# lv.net
KiCad netlist of a schematic drawn in Altium Designer
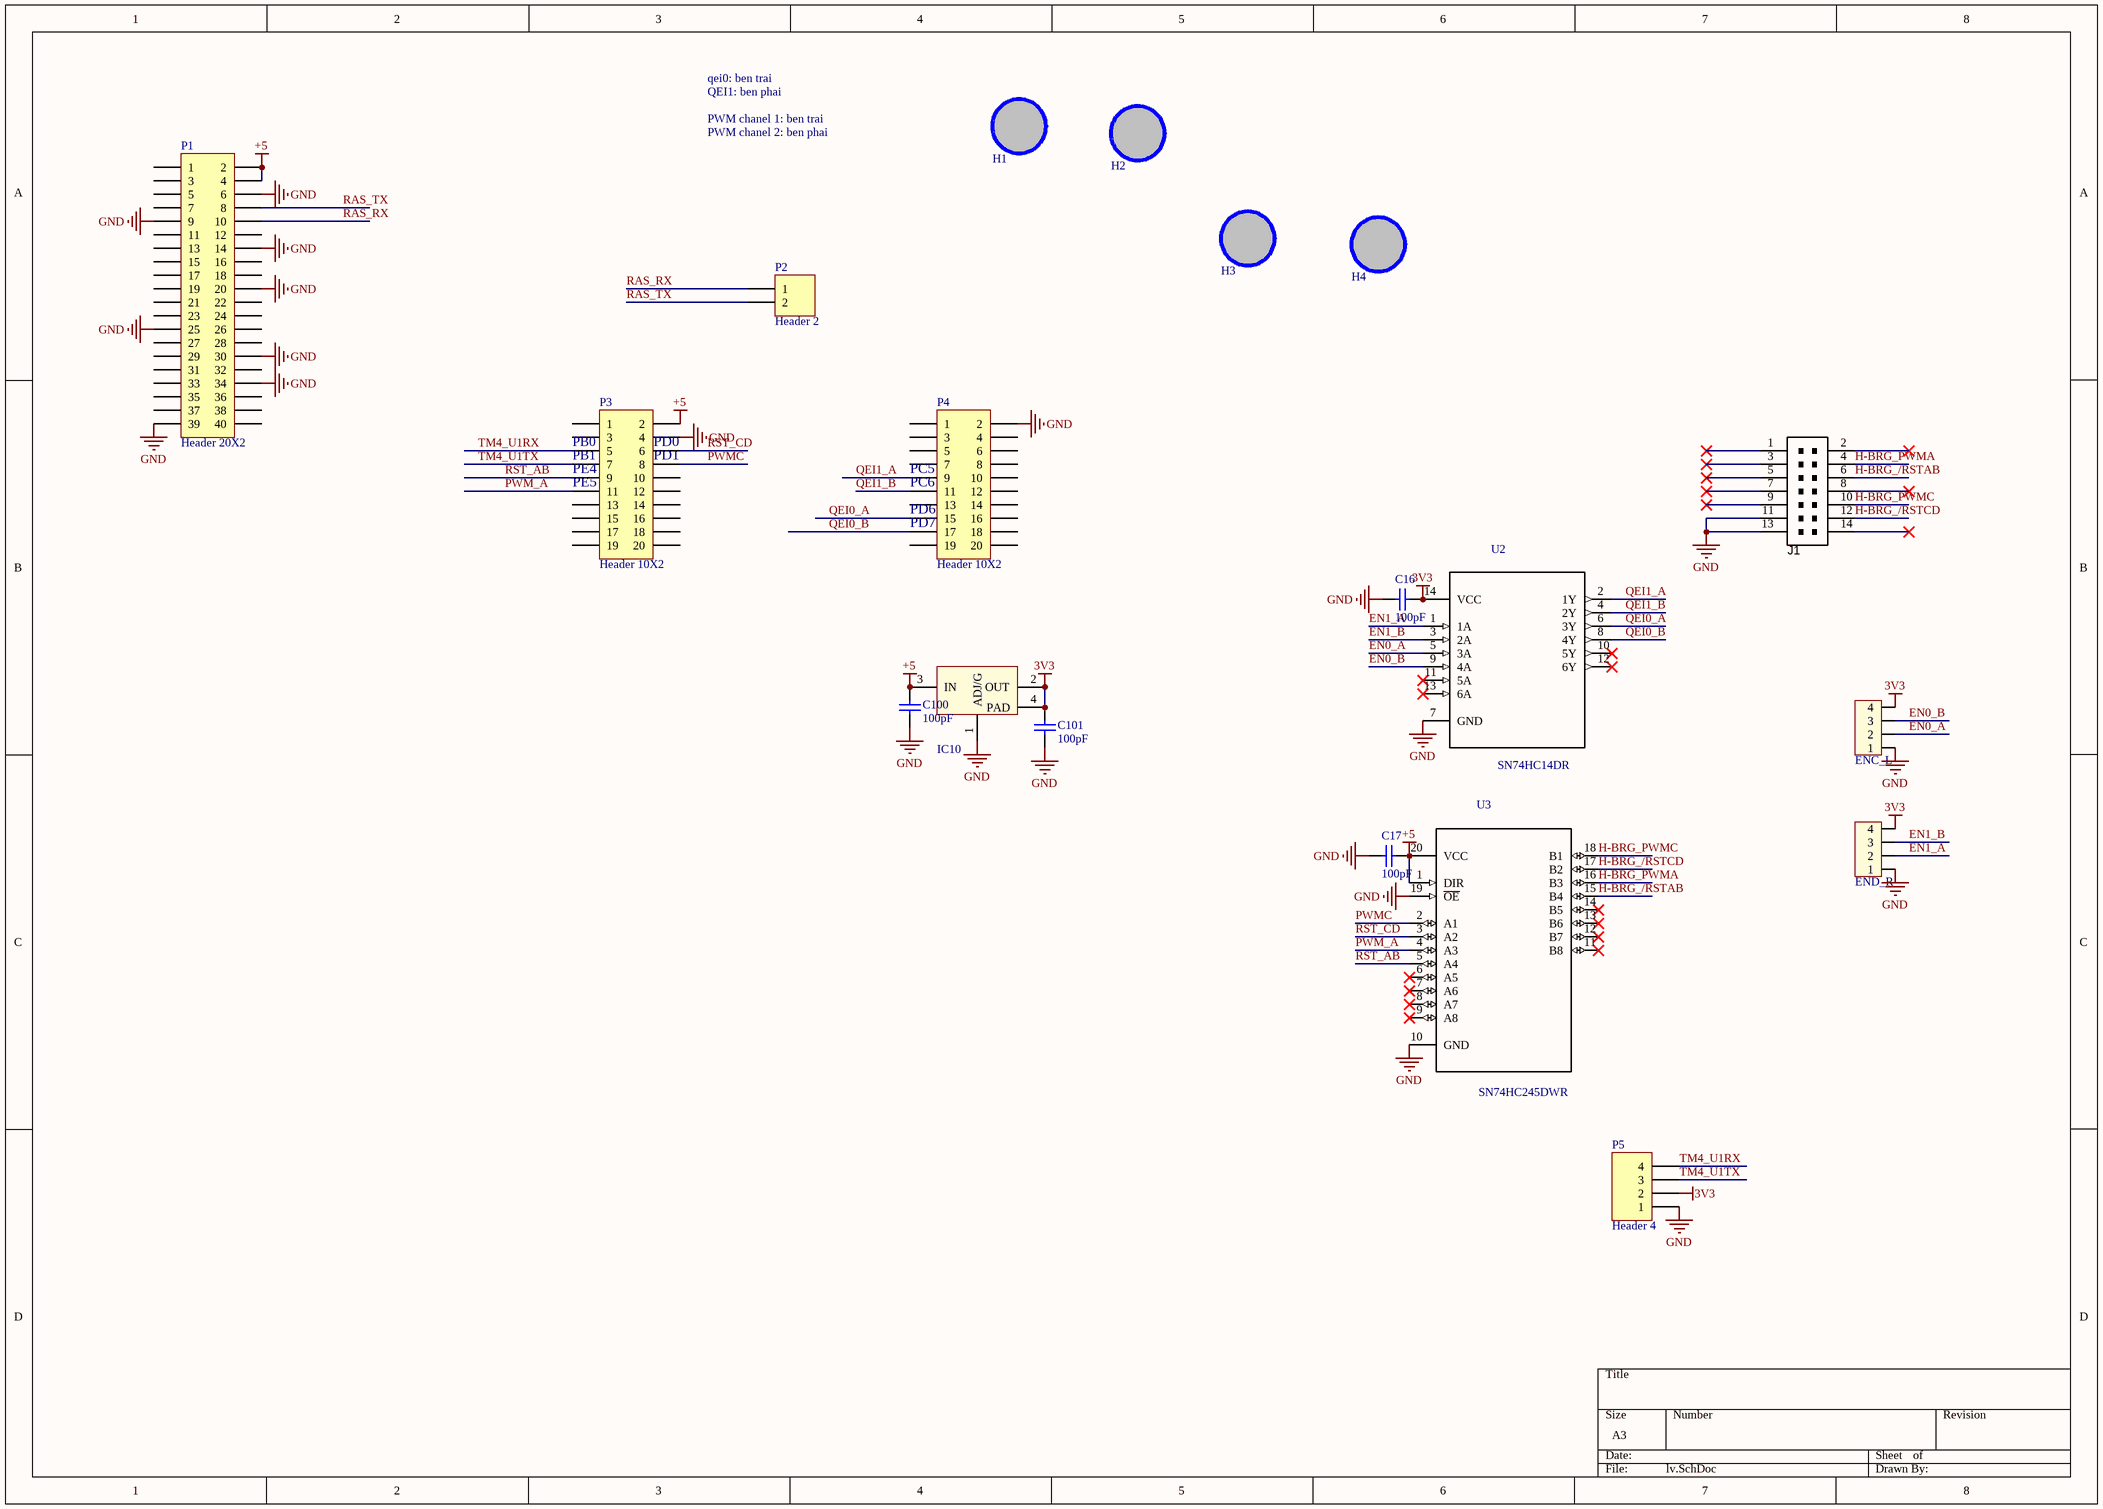
[diagram p0: lv.SchDoc]

(export (version "E")
  (design (tool "Eeschema 10.0.6"))
  (components
    (comp (ref "C16")
      (value "100pF")
      (footprint "CAP-SM-0805")
      (description "Capacitor")
      (fields (field (name "Comment") "Cap Non-Pol SMD"))
      (libsource (lib "PIF_Library") (part "Cap Non-Pol SMD"))
    )
    (comp (ref "C17")
      (value "100pF")
      (footprint "CAP-SM-0805")
      (description "Capacitor")
      (fields (field (name "Comment") "Cap Non-Pol SMD"))
      (libsource (lib "PIF_Library") (part "Cap Non-Pol SMD"))
    )
    (comp (ref "C100")
      (value "100pF")
      (footprint "CAP-SM-0805")
      (description "Capacitor")
      (fields (field (name "Comment") "Cap Non-Pol SMD"))
      (libsource (lib "PIF_Library") (part "Cap Non-Pol SMD"))
    )
    (comp (ref "C101")
      (value "100pF")
      (footprint "CAP-SM-0805")
      (description "Capacitor")
      (fields (field (name "Comment") "Cap Non-Pol SMD"))
      (libsource (lib "PIF_Library") (part "Cap Non-Pol SMD"))
    )
    (comp (ref "ENC_L1")
      (value "ENC_L")
      (footprint "CON4")
      (description "Connector 4")
      (libsource (lib "tuanti1997qn") (part "Con4"))
    )
    (comp (ref "END_R1")
      (value "END_R")
      (footprint "CON4")
      (description "Connector 4")
      (libsource (lib "tuanti1997qn") (part "Con4"))
    )
    (comp (ref "H1")
      (value "Hole")
      (footprint "LO KHOAN 3MM")
      (description "Hole 3mm")
      (libsource (lib "PIF_Library") (part "Hole"))
    )
    (comp (ref "H2")
      (value "Hole")
      (footprint "LO KHOAN 3MM")
      (description "Hole 3mm")
      (libsource (lib "PIF_Library") (part "Hole"))
    )
    (comp (ref "H3")
      (value "Hole")
      (footprint "LO KHOAN 3MM")
      (description "Hole 3mm")
      (libsource (lib "PIF_Library") (part "Hole"))
    )
    (comp (ref "H4")
      (value "Hole")
      (footprint "LO KHOAN 3MM")
      (description "Hole 3mm")
      (libsource (lib "PIF_Library") (part "Hole"))
    )
    (comp (ref "IC10")
      (value "LM1117")
      (footprint "SOT223-4N")
      (description "Available in 1.8V, 2.5V, 2.85V, 3.3V, 5V, and  Adjustable Versions")
      (libsource (lib "PIF_Library") (part "LM1117"))
    )
    (comp (ref "J1")
      (value "shrouded box header")
      (footprint "14P_PCB_HEADER_BRD_MNT_RA")
      (description "Header THD 14 POS Double-row right-angle 2.54mm pitch")
      (libsource (lib "tuanti1997qn") (part "CONN_HEADER_2x7P_RA_0.100in_Male"))
    )
    (comp (ref "P1")
      (value "Header 20X2")
      (footprint "HDR2X20")
      (description "Header, 20-Pin, Dual row")
      (fields (field (name "PUBLISHER") "Altium Limited"))
      (libsource (lib "Miscellaneous Connectors") (part "Header 20X2"))
    )
    (comp (ref "P2")
      (value "Header 2")
      (footprint "HDR1X2")
      (description "Header, 2-Pin")
      (fields (field (name "PUBLISHER") "Altium Limited"))
      (libsource (lib "Miscellaneous Connectors") (part "Header 2"))
    )
    (comp (ref "P3")
      (value "Header 10X2")
      (footprint "HDR2X10")
      (description "Header, 10-Pin, Dual row")
      (fields (field (name "PUBLISHER") "Altium Limited"))
      (libsource (lib "Miscellaneous Connectors") (part "Header 10X2"))
    )
    (comp (ref "P4")
      (value "Header 10X2")
      (footprint "HDR2X10")
      (description "Header, 10-Pin, Dual row")
      (fields (field (name "PUBLISHER") "Altium Limited"))
      (libsource (lib "Miscellaneous Connectors") (part "Header 10X2"))
    )
    (comp (ref "P5")
      (value "Header 4")
      (footprint "HDR1X4")
      (description "Header, 4-Pin")
      (fields (field (name "PUBLISHER") "Altium Limited"))
      (libsource (lib "Miscellaneous Connectors") (part "Header 4"))
    )
    (comp (ref "U2")
      (value "SN74HC14DR")
      (footprint "*SOIC127P600X175-14N")
      (description "Inverter Schmitt Trigger 6-Element CMOS 14-Pin SOIC T/R")
      (fields (field (name "MF") "Texas Instruments"))
      (libsource (lib "SN74HC14DR") (part "SN74HC14DR"))
    )
    (comp (ref "U3")
      (value "SN74HC245DWR")
      (footprint "*SOIC127P1030X265-20N")
      (description "Logic IC - Receiver, transceiver Texas Instruments SN74HC245DWR SOIC 20")
      (fields (field (name "MF") "Texas Instruments"))
      (libsource (lib "SN74HC245DWR") (part "SN74HC245DWR"))
    )
  )
  (nets
    (net (code "1") (name "+5") (class "Default")
      (node (ref "C100") (pin "2") (pinfunction "2_2") (pintype "passive"))
      (node (ref "C17") (pin "1") (pinfunction "1_1") (pintype "passive"))
      (node (ref "IC10") (pin "3") (pinfunction "IN_3") (pintype "passive"))
      (node (ref "P1") (pin "2") (pinfunction "2_2") (pintype "passive"))
      (node (ref "P1") (pin "4") (pinfunction "4_4") (pintype "passive"))
      (node (ref "P3") (pin "2") (pinfunction "2_2") (pintype "passive"))
      (node (ref "U3") (pin "1") (pinfunction "DIR_1") (pintype "input"))
      (node (ref "U3") (pin "20") (pinfunction "VCC_20") (pintype "power_in"))
    )
    (net (code "2") (name "/EN0_A") (class "Default")
      (node (ref "ENC_L1") (pin "2") (pinfunction "2_2") (pintype "passive"))
      (node (ref "U2") (pin "5") (pinfunction "3A_5") (pintype "input"))
    )
    (net (code "3") (name "/EN0_B") (class "Default")
      (node (ref "ENC_L1") (pin "3") (pinfunction "3_3") (pintype "passive"))
      (node (ref "U2") (pin "9") (pinfunction "4A_9") (pintype "input"))
    )
    (net (code "4") (name "/EN1_A") (class "Default")
      (node (ref "END_R1") (pin "2") (pinfunction "2_2") (pintype "passive"))
      (node (ref "U2") (pin "1") (pinfunction "1A_1") (pintype "input"))
    )
    (net (code "5") (name "/EN1_B") (class "Default")
      (node (ref "END_R1") (pin "3") (pinfunction "3_3") (pintype "passive"))
      (node (ref "U2") (pin "3") (pinfunction "2A_3") (pintype "input"))
    )
    (net (code "6") (name "/H-BRG_PWMA") (class "Default")
      (node (ref "J1") (pin "4") (pinfunction "4_4") (pintype "passive"))
      (node (ref "U3") (pin "16") (pinfunction "B3_16") (pintype "bidirectional"))
    )
    (net (code "7") (name "/H-BRG_PWMC") (class "Default")
      (node (ref "J1") (pin "10") (pinfunction "10_10") (pintype "passive"))
      (node (ref "U3") (pin "18") (pinfunction "B1_18") (pintype "bidirectional"))
    )
    (net (code "8") (name "/H-BRG_{slash}RSTAB") (class "Default")
      (node (ref "J1") (pin "6") (pinfunction "6_6") (pintype "passive"))
      (node (ref "U3") (pin "15") (pinfunction "B4_15") (pintype "bidirectional"))
    )
    (net (code "9") (name "/H-BRG_{slash}RSTCD") (class "Default")
      (node (ref "J1") (pin "12") (pinfunction "12_12") (pintype "passive"))
      (node (ref "U3") (pin "17") (pinfunction "B2_17") (pintype "bidirectional"))
    )
    (net (code "10") (name "/PWMC") (class "Default")
      (node (ref "P3") (pin "8") (pinfunction "8_8") (pintype "passive"))
      (node (ref "U3") (pin "2") (pinfunction "A1_2") (pintype "bidirectional"))
    )
    (net (code "11") (name "/PWM_A") (class "Default")
      (node (ref "P3") (pin "11") (pinfunction "11_11") (pintype "passive"))
      (node (ref "U3") (pin "4") (pinfunction "A3_4") (pintype "bidirectional"))
    )
    (net (code "12") (name "/QEI0_A") (class "Default")
      (node (ref "P4") (pin "15") (pinfunction "15_15") (pintype "passive"))
      (node (ref "U2") (pin "6") (pinfunction "3Y_6") (pintype "output"))
    )
    (net (code "13") (name "/QEI0_B") (class "Default")
      (node (ref "P4") (pin "17") (pinfunction "17_17") (pintype "passive"))
      (node (ref "U2") (pin "8") (pinfunction "4Y_8") (pintype "output"))
    )
    (net (code "14") (name "/QEI1_A") (class "Default")
      (node (ref "P4") (pin "9") (pinfunction "9_9") (pintype "passive"))
      (node (ref "U2") (pin "2") (pinfunction "1Y_2") (pintype "output"))
    )
    (net (code "15") (name "/QEI1_B") (class "Default")
      (node (ref "P4") (pin "11") (pinfunction "11_11") (pintype "passive"))
      (node (ref "U2") (pin "4") (pinfunction "2Y_4") (pintype "output"))
    )
    (net (code "16") (name "/RAS_RX") (class "Default")
      (node (ref "P1") (pin "10") (pinfunction "10_10") (pintype "passive"))
      (node (ref "P2") (pin "1") (pinfunction "1_1") (pintype "passive"))
    )
    (net (code "17") (name "/RAS_TX") (class "Default")
      (node (ref "P1") (pin "8") (pinfunction "8_8") (pintype "passive"))
      (node (ref "P2") (pin "2") (pinfunction "2_2") (pintype "passive"))
    )
    (net (code "18") (name "/RST_AB") (class "Default")
      (node (ref "P3") (pin "9") (pinfunction "9_9") (pintype "passive"))
      (node (ref "U3") (pin "5") (pinfunction "A4_5") (pintype "bidirectional"))
    )
    (net (code "19") (name "/RST_CD") (class "Default")
      (node (ref "P3") (pin "6") (pinfunction "6_6") (pintype "passive"))
      (node (ref "U3") (pin "3") (pinfunction "A2_3") (pintype "bidirectional"))
    )
    (net (code "20") (name "/TM4_U1RX") (class "Default")
      (node (ref "P3") (pin "5") (pinfunction "5_5") (pintype "passive"))
      (node (ref "P5") (pin "4") (pinfunction "4_4") (pintype "passive"))
    )
    (net (code "21") (name "/TM4_U1TX") (class "Default")
      (node (ref "P3") (pin "7") (pinfunction "7_7") (pintype "passive"))
      (node (ref "P5") (pin "3") (pinfunction "3_3") (pintype "passive"))
    )
    (net (code "22") (name "3V3") (class "Default")
      (node (ref "C101") (pin "2") (pinfunction "2_2") (pintype "passive"))
      (node (ref "C16") (pin "1") (pinfunction "1_1") (pintype "passive"))
      (node (ref "ENC_L1") (pin "4") (pinfunction "4_4") (pintype "passive"))
      (node (ref "END_R1") (pin "4") (pinfunction "4_4") (pintype "passive"))
      (node (ref "IC10") (pin "2") (pinfunction "OUT_2") (pintype "passive"))
      (node (ref "IC10") (pin "4") (pinfunction "PAD_4") (pintype "passive"))
      (node (ref "P5") (pin "2") (pinfunction "2_2") (pintype "passive"))
      (node (ref "U2") (pin "14") (pinfunction "VCC_14") (pintype "power_in"))
    )
    (net (code "23") (name "GND") (class "Default")
      (node (ref "C100") (pin "1") (pinfunction "1_1") (pintype "passive"))
      (node (ref "C101") (pin "1") (pinfunction "1_1") (pintype "passive"))
      (node (ref "C16") (pin "2") (pinfunction "2_2") (pintype "passive"))
      (node (ref "C17") (pin "2") (pinfunction "2_2") (pintype "passive"))
      (node (ref "ENC_L1") (pin "1") (pinfunction "1_1") (pintype "passive"))
      (node (ref "END_R1") (pin "1") (pinfunction "1_1") (pintype "passive"))
      (node (ref "IC10") (pin "1") (pinfunction "ADJ/G_1") (pintype "passive"))
      (node (ref "J1") (pin "11") (pinfunction "11_11") (pintype "passive"))
      (node (ref "J1") (pin "13") (pinfunction "13_13") (pintype "passive"))
      (node (ref "P1") (pin "14") (pinfunction "14_14") (pintype "passive"))
      (node (ref "P1") (pin "20") (pinfunction "20_20") (pintype "passive"))
      (node (ref "P1") (pin "25") (pinfunction "25_25") (pintype "passive"))
      (node (ref "P1") (pin "30") (pinfunction "30_30") (pintype "passive"))
      (node (ref "P1") (pin "34") (pinfunction "34_34") (pintype "passive"))
      (node (ref "P1") (pin "39") (pinfunction "39_39") (pintype "passive"))
      (node (ref "P1") (pin "6") (pinfunction "6_6") (pintype "passive"))
      (node (ref "P1") (pin "9") (pinfunction "9_9") (pintype "passive"))
      (node (ref "P3") (pin "4") (pinfunction "4_4") (pintype "passive"))
      (node (ref "P4") (pin "2") (pinfunction "2_2") (pintype "passive"))
      (node (ref "P5") (pin "1") (pinfunction "1_1") (pintype "passive"))
      (node (ref "U2") (pin "7") (pinfunction "GND_7") (pintype "passive"))
      (node (ref "U3") (pin "10") (pinfunction "GND_10") (pintype "passive"))
      (node (ref "U3") (pin "19") (pinfunction "~{OE}_19") (pintype "input"))
    )
    (net (code "24") (name "unconnected-(H1-Pad1)") (class "Default")
      (node (ref "H1") (pin "1") (pinfunction "1_1") (pintype "passive"))
    )
    (net (code "25") (name "unconnected-(H2-Pad1)") (class "Default")
      (node (ref "H2") (pin "1") (pinfunction "1_1") (pintype "passive"))
    )
    (net (code "26") (name "unconnected-(H3-Pad1)") (class "Default")
      (node (ref "H3") (pin "1") (pinfunction "1_1") (pintype "passive"))
    )
    (net (code "27") (name "unconnected-(H4-Pad1)") (class "Default")
      (node (ref "H4") (pin "1") (pinfunction "1_1") (pintype "passive"))
    )
    (net (code "28") (name "unconnected-(J1-Pad1)") (class "Default")
      (node (ref "J1") (pin "1") (pinfunction "1_1") (pintype "passive+no_connect"))
    )
    (net (code "29") (name "unconnected-(J1-Pad2)") (class "Default")
      (node (ref "J1") (pin "2") (pinfunction "2_2") (pintype "passive+no_connect"))
    )
    (net (code "30") (name "unconnected-(J1-Pad3)") (class "Default")
      (node (ref "J1") (pin "3") (pinfunction "3_3") (pintype "passive+no_connect"))
    )
    (net (code "31") (name "unconnected-(J1-Pad5)") (class "Default")
      (node (ref "J1") (pin "5") (pinfunction "5_5") (pintype "passive+no_connect"))
    )
    (net (code "32") (name "unconnected-(J1-Pad7)") (class "Default")
      (node (ref "J1") (pin "7") (pinfunction "7_7") (pintype "passive+no_connect"))
    )
    (net (code "33") (name "unconnected-(J1-Pad8)") (class "Default")
      (node (ref "J1") (pin "8") (pinfunction "8_8") (pintype "passive+no_connect"))
    )
    (net (code "34") (name "unconnected-(J1-Pad9)") (class "Default")
      (node (ref "J1") (pin "9") (pinfunction "9_9") (pintype "passive+no_connect"))
    )
    (net (code "35") (name "unconnected-(J1-Pad14)") (class "Default")
      (node (ref "J1") (pin "14") (pinfunction "14_14") (pintype "passive+no_connect"))
    )
    (net (code "36") (name "unconnected-(P1-Pad1)") (class "Default")
      (node (ref "P1") (pin "1") (pinfunction "1_1") (pintype "passive"))
    )
    (net (code "37") (name "unconnected-(P1-Pad3)") (class "Default")
      (node (ref "P1") (pin "3") (pinfunction "3_3") (pintype "passive"))
    )
    (net (code "38") (name "unconnected-(P1-Pad5)") (class "Default")
      (node (ref "P1") (pin "5") (pinfunction "5_5") (pintype "passive"))
    )
    (net (code "39") (name "unconnected-(P1-Pad7)") (class "Default")
      (node (ref "P1") (pin "7") (pinfunction "7_7") (pintype "passive"))
    )
    (net (code "40") (name "unconnected-(P1-Pad11)") (class "Default")
      (node (ref "P1") (pin "11") (pinfunction "11_11") (pintype "passive"))
    )
    (net (code "41") (name "unconnected-(P1-Pad12)") (class "Default")
      (node (ref "P1") (pin "12") (pinfunction "12_12") (pintype "passive"))
    )
    (net (code "42") (name "unconnected-(P1-Pad13)") (class "Default")
      (node (ref "P1") (pin "13") (pinfunction "13_13") (pintype "passive"))
    )
    (net (code "43") (name "unconnected-(P1-Pad15)") (class "Default")
      (node (ref "P1") (pin "15") (pinfunction "15_15") (pintype "passive"))
    )
    (net (code "44") (name "unconnected-(P1-Pad16)") (class "Default")
      (node (ref "P1") (pin "16") (pinfunction "16_16") (pintype "passive"))
    )
    (net (code "45") (name "unconnected-(P1-Pad17)") (class "Default")
      (node (ref "P1") (pin "17") (pinfunction "17_17") (pintype "passive"))
    )
    (net (code "46") (name "unconnected-(P1-Pad18)") (class "Default")
      (node (ref "P1") (pin "18") (pinfunction "18_18") (pintype "passive"))
    )
    (net (code "47") (name "unconnected-(P1-Pad19)") (class "Default")
      (node (ref "P1") (pin "19") (pinfunction "19_19") (pintype "passive"))
    )
    (net (code "48") (name "unconnected-(P1-Pad21)") (class "Default")
      (node (ref "P1") (pin "21") (pinfunction "21_21") (pintype "passive"))
    )
    (net (code "49") (name "unconnected-(P1-Pad22)") (class "Default")
      (node (ref "P1") (pin "22") (pinfunction "22_22") (pintype "passive"))
    )
    (net (code "50") (name "unconnected-(P1-Pad23)") (class "Default")
      (node (ref "P1") (pin "23") (pinfunction "23_23") (pintype "passive"))
    )
    (net (code "51") (name "unconnected-(P1-Pad24)") (class "Default")
      (node (ref "P1") (pin "24") (pinfunction "24_24") (pintype "passive"))
    )
    (net (code "52") (name "unconnected-(P1-Pad26)") (class "Default")
      (node (ref "P1") (pin "26") (pinfunction "26_26") (pintype "passive"))
    )
    (net (code "53") (name "unconnected-(P1-Pad27)") (class "Default")
      (node (ref "P1") (pin "27") (pinfunction "27_27") (pintype "passive"))
    )
    (net (code "54") (name "unconnected-(P1-Pad28)") (class "Default")
      (node (ref "P1") (pin "28") (pinfunction "28_28") (pintype "passive"))
    )
    (net (code "55") (name "unconnected-(P1-Pad29)") (class "Default")
      (node (ref "P1") (pin "29") (pinfunction "29_29") (pintype "passive"))
    )
    (net (code "56") (name "unconnected-(P1-Pad31)") (class "Default")
      (node (ref "P1") (pin "31") (pinfunction "31_31") (pintype "passive"))
    )
    (net (code "57") (name "unconnected-(P1-Pad32)") (class "Default")
      (node (ref "P1") (pin "32") (pinfunction "32_32") (pintype "passive"))
    )
    (net (code "58") (name "unconnected-(P1-Pad33)") (class "Default")
      (node (ref "P1") (pin "33") (pinfunction "33_33") (pintype "passive"))
    )
    (net (code "59") (name "unconnected-(P1-Pad35)") (class "Default")
      (node (ref "P1") (pin "35") (pinfunction "35_35") (pintype "passive"))
    )
    (net (code "60") (name "unconnected-(P1-Pad36)") (class "Default")
      (node (ref "P1") (pin "36") (pinfunction "36_36") (pintype "passive"))
    )
    (net (code "61") (name "unconnected-(P1-Pad37)") (class "Default")
      (node (ref "P1") (pin "37") (pinfunction "37_37") (pintype "passive"))
    )
    (net (code "62") (name "unconnected-(P1-Pad38)") (class "Default")
      (node (ref "P1") (pin "38") (pinfunction "38_38") (pintype "passive"))
    )
    (net (code "63") (name "unconnected-(P1-Pad40)") (class "Default")
      (node (ref "P1") (pin "40") (pinfunction "40_40") (pintype "passive"))
    )
    (net (code "64") (name "unconnected-(P3-Pad1)") (class "Default")
      (node (ref "P3") (pin "1") (pinfunction "1_1") (pintype "passive"))
    )
    (net (code "65") (name "unconnected-(P3-Pad3)") (class "Default")
      (node (ref "P3") (pin "3") (pinfunction "3_3") (pintype "passive"))
    )
    (net (code "66") (name "unconnected-(P3-Pad10)") (class "Default")
      (node (ref "P3") (pin "10") (pinfunction "10_10") (pintype "passive"))
    )
    (net (code "67") (name "unconnected-(P3-Pad12)") (class "Default")
      (node (ref "P3") (pin "12") (pinfunction "12_12") (pintype "passive"))
    )
    (net (code "68") (name "unconnected-(P3-Pad13)") (class "Default")
      (node (ref "P3") (pin "13") (pinfunction "13_13") (pintype "passive"))
    )
    (net (code "69") (name "unconnected-(P3-Pad14)") (class "Default")
      (node (ref "P3") (pin "14") (pinfunction "14_14") (pintype "passive"))
    )
    (net (code "70") (name "unconnected-(P3-Pad15)") (class "Default")
      (node (ref "P3") (pin "15") (pinfunction "15_15") (pintype "passive"))
    )
    (net (code "71") (name "unconnected-(P3-Pad16)") (class "Default")
      (node (ref "P3") (pin "16") (pinfunction "16_16") (pintype "passive"))
    )
    (net (code "72") (name "unconnected-(P3-Pad17)") (class "Default")
      (node (ref "P3") (pin "17") (pinfunction "17_17") (pintype "passive"))
    )
    (net (code "73") (name "unconnected-(P3-Pad18)") (class "Default")
      (node (ref "P3") (pin "18") (pinfunction "18_18") (pintype "passive"))
    )
    (net (code "74") (name "unconnected-(P3-Pad19)") (class "Default")
      (node (ref "P3") (pin "19") (pinfunction "19_19") (pintype "passive"))
    )
    (net (code "75") (name "unconnected-(P3-Pad20)") (class "Default")
      (node (ref "P3") (pin "20") (pinfunction "20_20") (pintype "passive"))
    )
    (net (code "76") (name "unconnected-(P4-Pad1)") (class "Default")
      (node (ref "P4") (pin "1") (pinfunction "1_1") (pintype "passive"))
    )
    (net (code "77") (name "unconnected-(P4-Pad3)") (class "Default")
      (node (ref "P4") (pin "3") (pinfunction "3_3") (pintype "passive"))
    )
    (net (code "78") (name "unconnected-(P4-Pad4)") (class "Default")
      (node (ref "P4") (pin "4") (pinfunction "4_4") (pintype "passive"))
    )
    (net (code "79") (name "unconnected-(P4-Pad5)") (class "Default")
      (node (ref "P4") (pin "5") (pinfunction "5_5") (pintype "passive"))
    )
    (net (code "80") (name "unconnected-(P4-Pad6)") (class "Default")
      (node (ref "P4") (pin "6") (pinfunction "6_6") (pintype "passive"))
    )
    (net (code "81") (name "unconnected-(P4-Pad7)") (class "Default")
      (node (ref "P4") (pin "7") (pinfunction "7_7") (pintype "passive"))
    )
    (net (code "82") (name "unconnected-(P4-Pad8)") (class "Default")
      (node (ref "P4") (pin "8") (pinfunction "8_8") (pintype "passive"))
    )
    (net (code "83") (name "unconnected-(P4-Pad10)") (class "Default")
      (node (ref "P4") (pin "10") (pinfunction "10_10") (pintype "passive"))
    )
    (net (code "84") (name "unconnected-(P4-Pad12)") (class "Default")
      (node (ref "P4") (pin "12") (pinfunction "12_12") (pintype "passive"))
    )
    (net (code "85") (name "unconnected-(P4-Pad13)") (class "Default")
      (node (ref "P4") (pin "13") (pinfunction "13_13") (pintype "passive"))
    )
    (net (code "86") (name "unconnected-(P4-Pad14)") (class "Default")
      (node (ref "P4") (pin "14") (pinfunction "14_14") (pintype "passive"))
    )
    (net (code "87") (name "unconnected-(P4-Pad16)") (class "Default")
      (node (ref "P4") (pin "16") (pinfunction "16_16") (pintype "passive"))
    )
    (net (code "88") (name "unconnected-(P4-Pad18)") (class "Default")
      (node (ref "P4") (pin "18") (pinfunction "18_18") (pintype "passive"))
    )
    (net (code "89") (name "unconnected-(P4-Pad19)") (class "Default")
      (node (ref "P4") (pin "19") (pinfunction "19_19") (pintype "passive"))
    )
    (net (code "90") (name "unconnected-(P4-Pad20)") (class "Default")
      (node (ref "P4") (pin "20") (pinfunction "20_20") (pintype "passive"))
    )
    (net (code "91") (name "unconnected-(U2-5A-Pad11)") (class "Default")
      (node (ref "U2") (pin "11") (pinfunction "5A_11") (pintype "input+no_connect"))
    )
    (net (code "92") (name "unconnected-(U2-5Y-Pad10)") (class "Default")
      (node (ref "U2") (pin "10") (pinfunction "5Y_10") (pintype "output+no_connect"))
    )
    (net (code "93") (name "unconnected-(U2-6A-Pad13)") (class "Default")
      (node (ref "U2") (pin "13") (pinfunction "6A_13") (pintype "input+no_connect"))
    )
    (net (code "94") (name "unconnected-(U2-6Y-Pad12)") (class "Default")
      (node (ref "U2") (pin "12") (pinfunction "6Y_12") (pintype "output+no_connect"))
    )
    (net (code "95") (name "unconnected-(U3-A5-Pad6)") (class "Default")
      (node (ref "U3") (pin "6") (pinfunction "A5_6") (pintype "bidirectional+no_connect"))
    )
    (net (code "96") (name "unconnected-(U3-A6-Pad7)") (class "Default")
      (node (ref "U3") (pin "7") (pinfunction "A6_7") (pintype "bidirectional+no_connect"))
    )
    (net (code "97") (name "unconnected-(U3-A7-Pad8)") (class "Default")
      (node (ref "U3") (pin "8") (pinfunction "A7_8") (pintype "bidirectional+no_connect"))
    )
    (net (code "98") (name "unconnected-(U3-A8-Pad9)") (class "Default")
      (node (ref "U3") (pin "9") (pinfunction "A8_9") (pintype "bidirectional+no_connect"))
    )
    (net (code "99") (name "unconnected-(U3-B5-Pad14)") (class "Default")
      (node (ref "U3") (pin "14") (pinfunction "B5_14") (pintype "bidirectional+no_connect"))
    )
    (net (code "100") (name "unconnected-(U3-B6-Pad13)") (class "Default")
      (node (ref "U3") (pin "13") (pinfunction "B6_13") (pintype "bidirectional+no_connect"))
    )
    (net (code "101") (name "unconnected-(U3-B7-Pad12)") (class "Default")
      (node (ref "U3") (pin "12") (pinfunction "B7_12") (pintype "bidirectional+no_connect"))
    )
    (net (code "102") (name "unconnected-(U3-B8-Pad11)") (class "Default")
      (node (ref "U3") (pin "11") (pinfunction "B8_11") (pintype "bidirectional+no_connect"))
    )
  )
)
